# noisegen.net
KiCad netlist of a schematic drawn in EAGLE
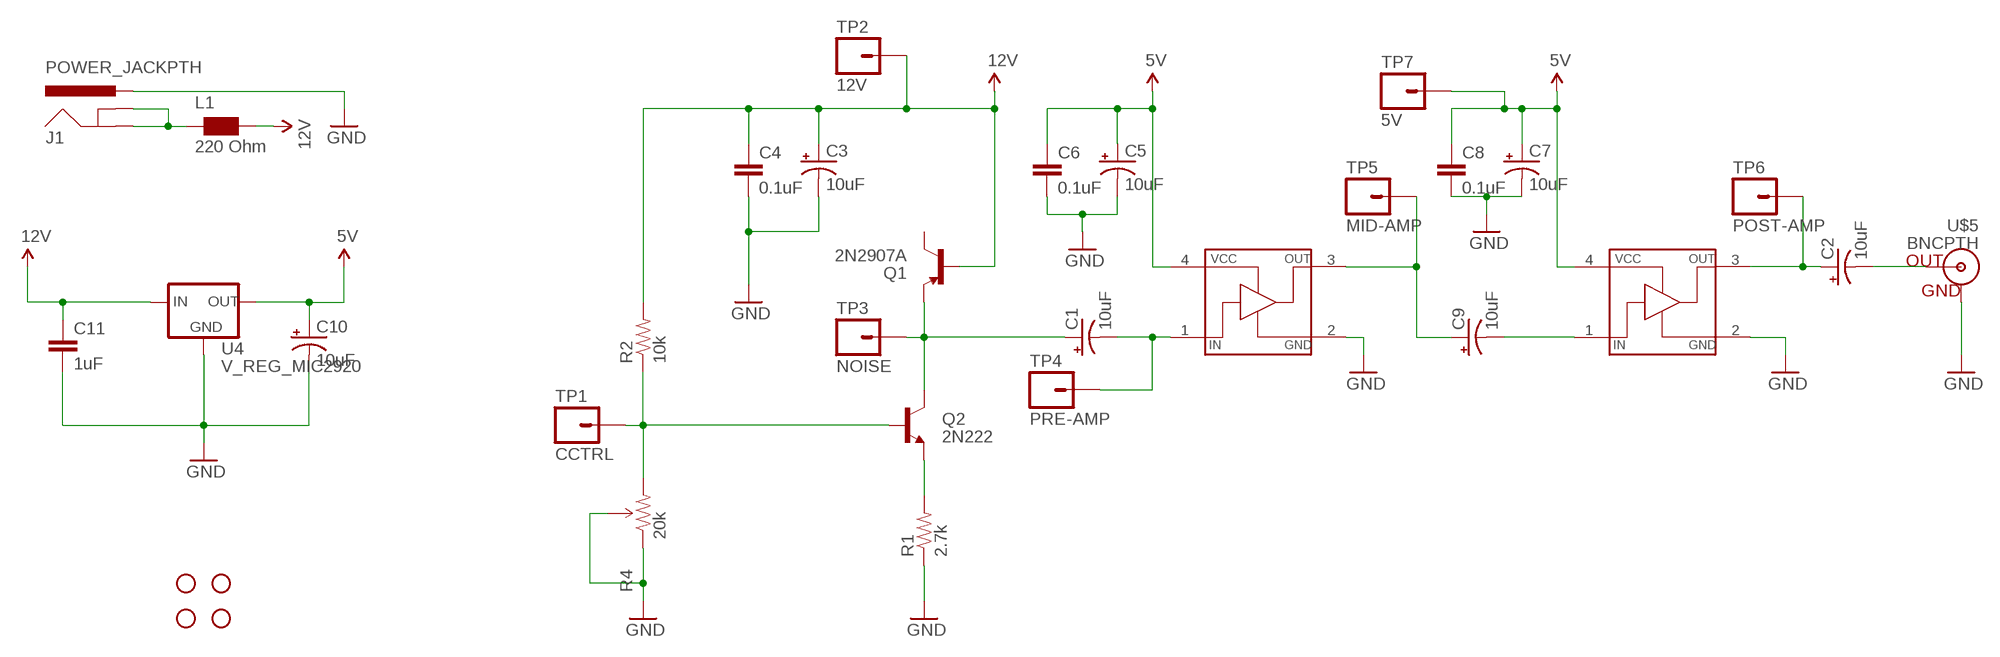
[diagram p0: schematic, sheet 1]

(export (version "E")
  (design (tool "Eeschema 10.0.6"))
  (components
    (comp (ref "C1")
      (value "10uF")
      (footprint "eagle-import:EIA3216")
      (libsource (lib "eagle-import") (part "CAP_POL1206"))
    )
    (comp (ref "C2")
      (value "10uF")
      (footprint "eagle-import:EIA3216")
      (libsource (lib "eagle-import") (part "CAP_POL1206"))
    )
    (comp (ref "C3")
      (value "10uF")
      (footprint "eagle-import:EIA3216")
      (libsource (lib "eagle-import") (part "CAP_POL1206"))
    )
    (comp (ref "C4")
      (value "0.1uF")
      (footprint "eagle-import:0603-CAP")
      (libsource (lib "eagle-import") (part "CAP0603-CAP"))
    )
    (comp (ref "C5")
      (value "10uF")
      (footprint "eagle-import:EIA3216")
      (libsource (lib "eagle-import") (part "CAP_POL1206"))
    )
    (comp (ref "C6")
      (value "0.1uF")
      (footprint "eagle-import:0603-CAP")
      (libsource (lib "eagle-import") (part "CAP0603-CAP"))
    )
    (comp (ref "C7")
      (value "10uF")
      (footprint "eagle-import:EIA3216")
      (libsource (lib "eagle-import") (part "CAP_POL1206"))
    )
    (comp (ref "C8")
      (value "0.1uF")
      (footprint "eagle-import:0603-CAP")
      (libsource (lib "eagle-import") (part "CAP0603-CAP"))
    )
    (comp (ref "C9")
      (value "10uF")
      (footprint "eagle-import:EIA3216")
      (libsource (lib "eagle-import") (part "CAP_POL1206"))
    )
    (comp (ref "C10")
      (value "10uF")
      (footprint "eagle-import:EIA3216")
      (libsource (lib "eagle-import") (part "CAP_POL1206"))
    )
    (comp (ref "C11")
      (value "1uF")
      (footprint "eagle-import:C0603")
      (libsource (lib "eagle-import") (part "C-EUC0603"))
    )
    (comp (ref "J1")
      (value "POWER_JACKPTH")
      (footprint "eagle-import:POWER_JACK_PTH")
      (libsource (lib "eagle-import") (part "POWER_JACKPTH"))
    )
    (comp (ref "JP1")
      (value "STAND-OFF")
      (footprint "eagle-import:STAND-OFF")
      (libsource (lib "eagle-import") (part "STAND-OFF"))
    )
    (comp (ref "JP2")
      (value "STAND-OFF")
      (footprint "eagle-import:STAND-OFF")
      (libsource (lib "eagle-import") (part "STAND-OFF"))
    )
    (comp (ref "JP3")
      (value "STAND-OFF")
      (footprint "eagle-import:STAND-OFF")
      (libsource (lib "eagle-import") (part "STAND-OFF"))
    )
    (comp (ref "JP4")
      (value "STAND-OFF")
      (footprint "eagle-import:STAND-OFF")
      (libsource (lib "eagle-import") (part "STAND-OFF"))
    )
    (comp (ref "L1")
      (value "220 Ohm")
      (footprint "eagle-import:0603")
      (libsource (lib "eagle-import") (part "WE-CBF_0603"))
    )
    (comp (ref "Q1")
      (value "2N2907A")
      (footprint "eagle-import:SOT23-3")
      (libsource (lib "eagle-import") (part "TRANSISTOR_PNPSMD"))
    )
    (comp (ref "Q2")
      (value "2N222")
      (footprint "eagle-import:SOT23-3")
      (libsource (lib "eagle-import") (part "TRANSISTOR_NPNSOT23-3"))
    )
    (comp (ref "R1")
      (value "2.7k")
      (footprint "eagle-import:0603-RES")
      (libsource (lib "eagle-import") (part "RESISTOR0603-RES"))
    )
    (comp (ref "R2")
      (value "10k")
      (footprint "eagle-import:0603-RES")
      (libsource (lib "eagle-import") (part "RESISTOR0603-RES"))
    )
    (comp (ref "R4")
      (value "20k")
      (footprint "eagle-import:3362U-2")
      (libsource (lib "eagle-import") (part "TRIMPOT"))
    )
    (comp (ref "TP1")
      (value "CCTRL")
      (footprint "eagle-import:1X01")
      (libsource (lib "eagle-import") (part "M01PTH"))
    )
    (comp (ref "TP2")
      (value "12V")
      (footprint "eagle-import:1X01")
      (libsource (lib "eagle-import") (part "M01PTH"))
    )
    (comp (ref "TP3")
      (value "NOISE")
      (footprint "eagle-import:1X01")
      (libsource (lib "eagle-import") (part "M01PTH"))
    )
    (comp (ref "TP4")
      (value "PRE-AMP")
      (footprint "eagle-import:1X01")
      (libsource (lib "eagle-import") (part "M01PTH"))
    )
    (comp (ref "TP5")
      (value "MID-AMP")
      (footprint "eagle-import:1X01")
      (libsource (lib "eagle-import") (part "M01PTH"))
    )
    (comp (ref "TP6")
      (value "POST-AMP")
      (footprint "eagle-import:1X01")
      (libsource (lib "eagle-import") (part "M01PTH"))
    )
    (comp (ref "TP7")
      (value "5V")
      (footprint "eagle-import:1X01")
      (libsource (lib "eagle-import") (part "M01PTH"))
    )
    (comp (ref "U$1")
      (value "MAX2650")
      (footprint "eagle-import:SOT143")
      (libsource (lib "eagle-import") (part "MAX2650"))
    )
    (comp (ref "U$2")
      (value "MAX2650")
      (footprint "eagle-import:SOT143")
      (libsource (lib "eagle-import") (part "MAX2650"))
    )
    (comp (ref "U$5")
      (value "BNCPTH")
      (footprint "eagle-import:BNC")
      (libsource (lib "eagle-import") (part "BNCPTH"))
    )
    (comp (ref "U4")
      (value "V_REG_MIC2920")
      (footprint "eagle-import:SOT223")
      (libsource (lib "eagle-import") (part "V_REG_MIC2920"))
    )
  )
  (nets
    (net (code "1") (name "5V") (class "Default")
      (node (ref "C10") (pin "A") (pinfunction "+_A") (pintype "passive"))
      (node (ref "C5") (pin "A") (pinfunction "+_A") (pintype "passive"))
      (node (ref "C6") (pin "1") (pinfunction "1_1") (pintype "passive"))
      (node (ref "C7") (pin "A") (pinfunction "+_A") (pintype "passive"))
      (node (ref "C8") (pin "1") (pinfunction "1_1") (pintype "passive"))
      (node (ref "TP7") (pin "1") (pinfunction "1_1") (pintype "passive"))
      (node (ref "U$1") (pin "4") (pinfunction "VCC_4") (pintype "power_in"))
      (node (ref "U$2") (pin "4") (pinfunction "VCC_4") (pintype "power_in"))
      (node (ref "U4") (pin "3") (pinfunction "OUT_3") (pintype "output"))
    )
    (net (code "2") (name "12V") (class "Default")
      (node (ref "C11") (pin "1") (pinfunction "1_1") (pintype "passive"))
      (node (ref "C3") (pin "A") (pinfunction "+_A") (pintype "passive"))
      (node (ref "C4") (pin "1") (pinfunction "1_1") (pintype "passive"))
      (node (ref "L1") (pin "2") (pinfunction "2_2") (pintype "passive"))
      (node (ref "Q1") (pin "1") (pinfunction "B_1") (pintype "passive"))
      (node (ref "R2") (pin "2") (pinfunction "2_2") (pintype "passive"))
      (node (ref "TP2") (pin "1") (pinfunction "1_1") (pintype "passive"))
      (node (ref "U4") (pin "1") (pinfunction "IN_1") (pintype "input"))
    )
    (net (code "3") (name "GND") (class "Default")
      (node (ref "C10") (pin "C") (pinfunction "-_C") (pintype "passive"))
      (node (ref "C11") (pin "2") (pinfunction "2_2") (pintype "passive"))
      (node (ref "C3") (pin "C") (pinfunction "-_C") (pintype "passive"))
      (node (ref "C4") (pin "2") (pinfunction "2_2") (pintype "passive"))
      (node (ref "C5") (pin "C") (pinfunction "-_C") (pintype "passive"))
      (node (ref "C6") (pin "2") (pinfunction "2_2") (pintype "passive"))
      (node (ref "C7") (pin "C") (pinfunction "-_C") (pintype "passive"))
      (node (ref "C8") (pin "2") (pinfunction "2_2") (pintype "passive"))
      (node (ref "J1") (pin "PWR") (pinfunction "PWR_PWR") (pintype "bidirectional"))
      (node (ref "R1") (pin "1") (pinfunction "1_1") (pintype "passive"))
      (node (ref "R4") (pin "1") (pinfunction "CCW_1") (pintype "passive"))
      (node (ref "R4") (pin "2") (pinfunction "WIPER_2") (pintype "passive"))
      (node (ref "U$1") (pin "2") (pinfunction "GND_2") (pintype "power_in"))
      (node (ref "U$2") (pin "2") (pinfunction "GND_2") (pintype "power_in"))
      (node (ref "U$5") (pin "GND") (pinfunction "GND_GND") (pintype "bidirectional"))
      (node (ref "U4") (pin "2") (pinfunction "GND_2") (pintype "input"))
    )
    (net (code "4") (name "Net-(C1-+)") (class "Default")
      (node (ref "C1") (pin "A") (pinfunction "+_A") (pintype "passive"))
      (node (ref "Q1") (pin "2") (pinfunction "E_2") (pintype "passive"))
      (node (ref "Q2") (pin "3") (pinfunction "C_3") (pintype "passive"))
      (node (ref "TP3") (pin "1") (pinfunction "1_1") (pintype "passive"))
    )
    (net (code "5") (name "Net-(C1--)") (class "Default")
      (node (ref "C1") (pin "C") (pinfunction "-_C") (pintype "passive"))
      (node (ref "TP4") (pin "1") (pinfunction "1_1") (pintype "passive"))
      (node (ref "U$1") (pin "1") (pinfunction "IN_1") (pintype "input"))
    )
    (net (code "6") (name "Net-(C2-+)") (class "Default")
      (node (ref "C2") (pin "A") (pinfunction "+_A") (pintype "passive"))
      (node (ref "TP6") (pin "1") (pinfunction "1_1") (pintype "passive"))
      (node (ref "U$2") (pin "3") (pinfunction "OUT_3") (pintype "output"))
    )
    (net (code "7") (name "Net-(C2--)") (class "Default")
      (node (ref "C2") (pin "C") (pinfunction "-_C") (pintype "passive"))
      (node (ref "U$5") (pin "S") (pinfunction "OUT_S") (pintype "bidirectional"))
    )
    (net (code "8") (name "Net-(C9-+)") (class "Default")
      (node (ref "C9") (pin "A") (pinfunction "+_A") (pintype "passive"))
      (node (ref "TP5") (pin "1") (pinfunction "1_1") (pintype "passive"))
      (node (ref "U$1") (pin "3") (pinfunction "OUT_3") (pintype "output"))
    )
    (net (code "9") (name "Net-(C9--)") (class "Default")
      (node (ref "C9") (pin "C") (pinfunction "-_C") (pintype "passive"))
      (node (ref "U$2") (pin "1") (pinfunction "IN_1") (pintype "input"))
    )
    (net (code "10") (name "Net-(J1-PadGND)") (class "Default")
      (node (ref "J1") (pin "GND") (pinfunction "GND_GND") (pintype "bidirectional"))
      (node (ref "J1") (pin "GNDBREAK") (pinfunction "GNDBREAK_GNDBREAK") (pintype "bidirectional"))
      (node (ref "L1") (pin "1") (pinfunction "1_1") (pintype "passive"))
    )
    (net (code "11") (name "Net-(Q2-B)") (class "Default")
      (node (ref "Q2") (pin "1") (pinfunction "B_1") (pintype "passive"))
      (node (ref "R2") (pin "1") (pinfunction "1_1") (pintype "passive"))
      (node (ref "R4") (pin "3") (pinfunction "CW_3") (pintype "passive"))
      (node (ref "TP1") (pin "1") (pinfunction "1_1") (pintype "passive"))
    )
    (net (code "12") (name "Net-(Q2-E)") (class "Default")
      (node (ref "Q2") (pin "2") (pinfunction "E_2") (pintype "passive"))
      (node (ref "R1") (pin "2") (pinfunction "2_2") (pintype "passive"))
    )
    (net (code "13") (name "unconnected-(Q1-C-Pad3)") (class "Default")
      (node (ref "Q1") (pin "3") (pinfunction "C_3") (pintype "passive"))
    )
  )
)
